# sdram_rev.net
KiCad netlist of a schematic drawn in Altium Designer
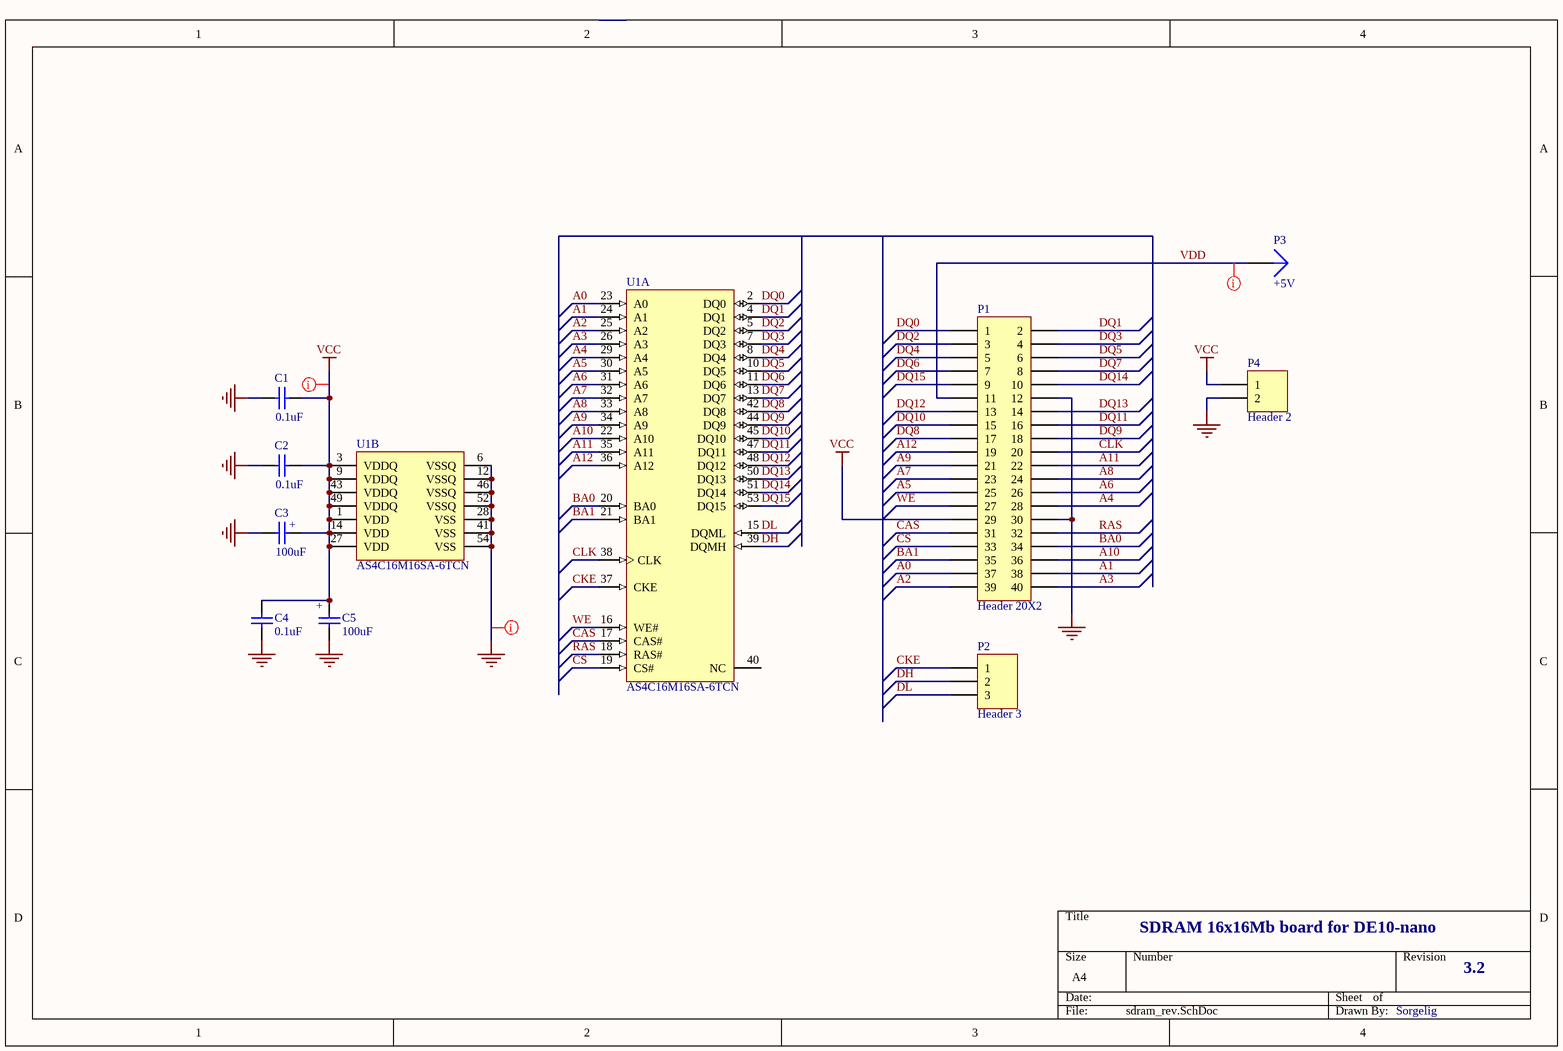
[diagram p0: sdram_rev.SchDoc]

(export (version "E")
  (design (tool "Eeschema 10.0.6"))
  (components
    (comp (ref "C1")
      (value "0.1uF")
      (footprint "0805")
      (description "Ceramic Chip Capacitor - Standard")
      (fields (field (name "Comment") "C0805") (field (name "PUBLISHER") "Altium Limited"))
      (libsource (lib "KEMET Chip Capacitor") (part "C0805"))
    )
    (comp (ref "C2")
      (value "0.1uF")
      (footprint "0805")
      (description "Ceramic Chip Capacitor - Standard")
      (fields (field (name "Comment") "C0805") (field (name "PUBLISHER") "Altium Limited"))
      (libsource (lib "KEMET Chip Capacitor") (part "C0805"))
    )
    (comp (ref "C3")
      (value "+")
      (footprint "0805")
      (description "Ceramic Chip Capacitor - Standard")
      (fields (field (name "ALTIUM_VALUE") "100uF") (field (name "PUBLISHER") "Altium Limited"))
      (libsource (lib "KEMET Chip Capacitor") (part "C0805"))
    )
    (comp (ref "C4")
      (value "0.1uF")
      (footprint "0805")
      (description "Ceramic Chip Capacitor - Standard")
      (fields (field (name "Comment") "C0805") (field (name "PUBLISHER") "Altium Limited"))
      (libsource (lib "KEMET Chip Capacitor") (part "C0805"))
    )
    (comp (ref "C5")
      (value "+")
      (footprint "0805")
      (description "Ceramic Chip Capacitor - Standard")
      (fields (field (name "ALTIUM_VALUE") "100uF") (field (name "PUBLISHER") "Altium Limited"))
      (libsource (lib "KEMET Chip Capacitor") (part "C0805"))
    )
    (comp (ref "P1")
      (value "Header 20X2")
      (footprint "HDR2X20")
      (description "Header, 20-Pin, Dual row")
      (fields (field (name "PUBLISHER") "Altium Limited"))
      (libsource (lib "Miscellaneous Connectors") (part "Header 20X2"))
    )
    (comp (ref "P2")
      (value "Header 3")
      (footprint "HDR1X3")
      (description "Header, 3-Pin")
      (fields (field (name "PUBLISHER") "Altium Limited"))
      (libsource (lib "Miscellaneous Connectors") (part "Header 3"))
    )
    (comp (ref "P3")
      (value "+5V")
      (footprint "PIN1")
      (description "Plug")
      (fields (field (name "PUBLISHER") "Altium Limited"))
      (libsource (lib "Miscellaneous Connectors") (part "Plug"))
    )
    (comp (ref "P4")
      (value "Header 2")
      (footprint "HDR1X2")
      (description "Header, 2-Pin")
      (fields (field (name "PUBLISHER") "Altium Limited"))
      (libsource (lib "Miscellaneous Connectors") (part "Header 2"))
    )
    (comp (ref "U1")
      (value "AS4C16M16SA-6TCN")
      (footprint "MICT-P-54_N")
      (description "256Mb PC133 SDR SDRAM, 16Mb x 16, 6ns, 3.3V, 0 to 70 degC, 54-Pin TSOP, Pb-Free")
      (fields (field (name "VOLTAGE") "3.3V ") (field (name "MANUFACTURER") "Micron"))
      (libsource (lib "Micron Memory SDRAM") (part "MT48LC16M16A2P-6A"))
    )
  )
  (nets
    (net (code "1") (name "/A0") (class "Default")
      (node (ref "P1") (pin "37") (pinfunction "37_37") (pintype "passive"))
      (node (ref "U1") (pin "23") (pinfunction "A0_23") (pintype "input"))
    )
    (net (code "2") (name "/A1") (class "Default")
      (node (ref "P1") (pin "38") (pinfunction "38_38") (pintype "passive"))
      (node (ref "U1") (pin "24") (pinfunction "A1_24") (pintype "input"))
    )
    (net (code "3") (name "/A2") (class "Default")
      (node (ref "P1") (pin "39") (pinfunction "39_39") (pintype "passive"))
      (node (ref "U1") (pin "25") (pinfunction "A2_25") (pintype "input"))
    )
    (net (code "4") (name "/A3") (class "Default")
      (node (ref "P1") (pin "40") (pinfunction "40_40") (pintype "passive"))
      (node (ref "U1") (pin "26") (pinfunction "A3_26") (pintype "input"))
    )
    (net (code "5") (name "/A4") (class "Default")
      (node (ref "P1") (pin "28") (pinfunction "28_28") (pintype "passive"))
      (node (ref "U1") (pin "29") (pinfunction "A4_29") (pintype "input"))
    )
    (net (code "6") (name "/A5") (class "Default")
      (node (ref "P1") (pin "25") (pinfunction "25_25") (pintype "passive"))
      (node (ref "U1") (pin "30") (pinfunction "A5_30") (pintype "input"))
    )
    (net (code "7") (name "/A6") (class "Default")
      (node (ref "P1") (pin "26") (pinfunction "26_26") (pintype "passive"))
      (node (ref "U1") (pin "31") (pinfunction "A6_31") (pintype "input"))
    )
    (net (code "8") (name "/A7") (class "Default")
      (node (ref "P1") (pin "23") (pinfunction "23_23") (pintype "passive"))
      (node (ref "U1") (pin "32") (pinfunction "A7_32") (pintype "input"))
    )
    (net (code "9") (name "/A8") (class "Default")
      (node (ref "P1") (pin "24") (pinfunction "24_24") (pintype "passive"))
      (node (ref "U1") (pin "33") (pinfunction "A8_33") (pintype "input"))
    )
    (net (code "10") (name "/A9") (class "Default")
      (node (ref "P1") (pin "21") (pinfunction "21_21") (pintype "passive"))
      (node (ref "U1") (pin "34") (pinfunction "A9_34") (pintype "input"))
    )
    (net (code "11") (name "/A10") (class "Default")
      (node (ref "P1") (pin "36") (pinfunction "36_36") (pintype "passive"))
      (node (ref "U1") (pin "22") (pinfunction "A10_22") (pintype "input"))
    )
    (net (code "12") (name "/A11") (class "Default")
      (node (ref "P1") (pin "22") (pinfunction "22_22") (pintype "passive"))
      (node (ref "U1") (pin "35") (pinfunction "A11_35") (pintype "input"))
    )
    (net (code "13") (name "/A12") (class "Default")
      (node (ref "P1") (pin "19") (pinfunction "19_19") (pintype "passive"))
      (node (ref "U1") (pin "36") (pinfunction "A12_36") (pintype "input"))
    )
    (net (code "14") (name "/BA0") (class "Default")
      (node (ref "P1") (pin "34") (pinfunction "34_34") (pintype "passive"))
      (node (ref "U1") (pin "20") (pinfunction "BA0_20") (pintype "input"))
    )
    (net (code "15") (name "/BA1") (class "Default")
      (node (ref "P1") (pin "35") (pinfunction "35_35") (pintype "passive"))
      (node (ref "U1") (pin "21") (pinfunction "BA1_21") (pintype "input"))
    )
    (net (code "16") (name "/CAS") (class "Default")
      (node (ref "P1") (pin "31") (pinfunction "31_31") (pintype "passive"))
      (node (ref "U1") (pin "17") (pinfunction "CAS#_17") (pintype "input"))
    )
    (net (code "17") (name "/CKE") (class "Default")
      (node (ref "P2") (pin "1") (pinfunction "1_1") (pintype "passive"))
      (node (ref "U1") (pin "37") (pinfunction "CKE_37") (pintype "input"))
    )
    (net (code "18") (name "/CLK") (class "Default")
      (node (ref "P1") (pin "20") (pinfunction "20_20") (pintype "passive"))
      (node (ref "U1") (pin "38") (pinfunction "CLK_38") (pintype "input"))
    )
    (net (code "19") (name "/CS") (class "Default")
      (node (ref "P1") (pin "33") (pinfunction "33_33") (pintype "passive"))
      (node (ref "U1") (pin "19") (pinfunction "CS#_19") (pintype "input"))
    )
    (net (code "20") (name "/DH") (class "Default")
      (node (ref "P2") (pin "2") (pinfunction "2_2") (pintype "passive"))
      (node (ref "U1") (pin "39") (pinfunction "DQMH_39") (pintype "input"))
    )
    (net (code "21") (name "/DL") (class "Default")
      (node (ref "P2") (pin "3") (pinfunction "3_3") (pintype "passive"))
      (node (ref "U1") (pin "15") (pinfunction "DQML_15") (pintype "input"))
    )
    (net (code "22") (name "/DQ0") (class "Default")
      (node (ref "P1") (pin "1") (pinfunction "1_1") (pintype "passive"))
      (node (ref "U1") (pin "2") (pinfunction "DQ0_2") (pintype "bidirectional"))
    )
    (net (code "23") (name "/DQ1") (class "Default")
      (node (ref "P1") (pin "2") (pinfunction "2_2") (pintype "passive"))
      (node (ref "U1") (pin "4") (pinfunction "DQ1_4") (pintype "bidirectional"))
    )
    (net (code "24") (name "/DQ2") (class "Default")
      (node (ref "P1") (pin "3") (pinfunction "3_3") (pintype "passive"))
      (node (ref "U1") (pin "5") (pinfunction "DQ2_5") (pintype "bidirectional"))
    )
    (net (code "25") (name "/DQ3") (class "Default")
      (node (ref "P1") (pin "4") (pinfunction "4_4") (pintype "passive"))
      (node (ref "U1") (pin "7") (pinfunction "DQ3_7") (pintype "bidirectional"))
    )
    (net (code "26") (name "/DQ4") (class "Default")
      (node (ref "P1") (pin "5") (pinfunction "5_5") (pintype "passive"))
      (node (ref "U1") (pin "8") (pinfunction "DQ4_8") (pintype "bidirectional"))
    )
    (net (code "27") (name "/DQ5") (class "Default")
      (node (ref "P1") (pin "6") (pinfunction "6_6") (pintype "passive"))
      (node (ref "U1") (pin "10") (pinfunction "DQ5_10") (pintype "bidirectional"))
    )
    (net (code "28") (name "/DQ6") (class "Default")
      (node (ref "P1") (pin "7") (pinfunction "7_7") (pintype "passive"))
      (node (ref "U1") (pin "11") (pinfunction "DQ6_11") (pintype "bidirectional"))
    )
    (net (code "29") (name "/DQ7") (class "Default")
      (node (ref "P1") (pin "8") (pinfunction "8_8") (pintype "passive"))
      (node (ref "U1") (pin "13") (pinfunction "DQ7_13") (pintype "bidirectional"))
    )
    (net (code "30") (name "/DQ8") (class "Default")
      (node (ref "P1") (pin "17") (pinfunction "17_17") (pintype "passive"))
      (node (ref "U1") (pin "42") (pinfunction "DQ8_42") (pintype "bidirectional"))
    )
    (net (code "31") (name "/DQ9") (class "Default")
      (node (ref "P1") (pin "18") (pinfunction "18_18") (pintype "passive"))
      (node (ref "U1") (pin "44") (pinfunction "DQ9_44") (pintype "bidirectional"))
    )
    (net (code "32") (name "/DQ10") (class "Default")
      (node (ref "P1") (pin "15") (pinfunction "15_15") (pintype "passive"))
      (node (ref "U1") (pin "45") (pinfunction "DQ10_45") (pintype "bidirectional"))
    )
    (net (code "33") (name "/DQ11") (class "Default")
      (node (ref "P1") (pin "16") (pinfunction "16_16") (pintype "passive"))
      (node (ref "U1") (pin "47") (pinfunction "DQ11_47") (pintype "bidirectional"))
    )
    (net (code "34") (name "/DQ12") (class "Default")
      (node (ref "P1") (pin "13") (pinfunction "13_13") (pintype "passive"))
      (node (ref "U1") (pin "48") (pinfunction "DQ12_48") (pintype "bidirectional"))
    )
    (net (code "35") (name "/DQ13") (class "Default")
      (node (ref "P1") (pin "14") (pinfunction "14_14") (pintype "passive"))
      (node (ref "U1") (pin "50") (pinfunction "DQ13_50") (pintype "bidirectional"))
    )
    (net (code "36") (name "/DQ14") (class "Default")
      (node (ref "P1") (pin "10") (pinfunction "10_10") (pintype "passive"))
      (node (ref "U1") (pin "51") (pinfunction "DQ14_51") (pintype "bidirectional"))
    )
    (net (code "37") (name "/DQ15") (class "Default")
      (node (ref "P1") (pin "9") (pinfunction "9_9") (pintype "passive"))
      (node (ref "U1") (pin "53") (pinfunction "DQ15_53") (pintype "bidirectional"))
    )
    (net (code "38") (name "/RAS") (class "Default")
      (node (ref "P1") (pin "32") (pinfunction "32_32") (pintype "passive"))
      (node (ref "U1") (pin "18") (pinfunction "RAS#_18") (pintype "input"))
    )
    (net (code "39") (name "/VDD") (class "Default")
      (node (ref "P1") (pin "11") (pinfunction "11_11") (pintype "power_in"))
      (node (ref "P3") (pin "1") (pinfunction "1_1") (pintype "passive"))
    )
    (net (code "40") (name "/WE") (class "Default")
      (node (ref "P1") (pin "27") (pinfunction "27_27") (pintype "passive"))
      (node (ref "U1") (pin "16") (pinfunction "WE#_16") (pintype "input"))
    )
    (net (code "41") (name "GND") (class "Default")
      (node (ref "C1") (pin "1") (pinfunction "1_1") (pintype "passive"))
      (node (ref "C2") (pin "1") (pinfunction "1_1") (pintype "passive"))
      (node (ref "C3") (pin "1") (pinfunction "1_1") (pintype "passive"))
      (node (ref "C4") (pin "1") (pinfunction "1_1") (pintype "passive"))
      (node (ref "C5") (pin "1") (pinfunction "1_1") (pintype "passive"))
      (node (ref "P1") (pin "12") (pinfunction "12_12") (pintype "power_in"))
      (node (ref "P1") (pin "30") (pinfunction "30_30") (pintype "power_in"))
      (node (ref "P4") (pin "2") (pinfunction "2_2") (pintype "passive"))
      (node (ref "U1") (pin "12") (pinfunction "VSSQ_12") (pintype "power_in"))
      (node (ref "U1") (pin "28") (pinfunction "VSS_28") (pintype "power_in"))
      (node (ref "U1") (pin "41") (pinfunction "VSS_41") (pintype "power_in"))
      (node (ref "U1") (pin "46") (pinfunction "VSSQ_46") (pintype "power_in"))
      (node (ref "U1") (pin "52") (pinfunction "VSSQ_52") (pintype "power_in"))
      (node (ref "U1") (pin "54") (pinfunction "VSS_54") (pintype "power_in"))
      (node (ref "U1") (pin "6") (pinfunction "VSSQ_6") (pintype "power_in"))
    )
    (net (code "42") (name "VCC") (class "Default")
      (node (ref "C1") (pin "2") (pinfunction "2_2") (pintype "passive"))
      (node (ref "C2") (pin "2") (pinfunction "2_2") (pintype "passive"))
      (node (ref "C3") (pin "2") (pinfunction "2_2") (pintype "passive"))
      (node (ref "C4") (pin "2") (pinfunction "2_2") (pintype "passive"))
      (node (ref "C5") (pin "2") (pinfunction "2_2") (pintype "passive"))
      (node (ref "P1") (pin "29") (pinfunction "29_29") (pintype "power_in"))
      (node (ref "P4") (pin "1") (pinfunction "1_1") (pintype "passive"))
      (node (ref "U1") (pin "1") (pinfunction "VDD_1") (pintype "power_in"))
      (node (ref "U1") (pin "14") (pinfunction "VDD_14") (pintype "power_in"))
      (node (ref "U1") (pin "27") (pinfunction "VDD_27") (pintype "power_in"))
      (node (ref "U1") (pin "3") (pinfunction "VDDQ_3") (pintype "power_in"))
      (node (ref "U1") (pin "43") (pinfunction "VDDQ_43") (pintype "power_in"))
      (node (ref "U1") (pin "49") (pinfunction "VDDQ_49") (pintype "power_in"))
      (node (ref "U1") (pin "9") (pinfunction "VDDQ_9") (pintype "power_in"))
    )
    (net (code "43") (name "unconnected-(U1A-NC-Pad40)") (class "Default")
      (node (ref "U1") (pin "40") (pinfunction "NC_40") (pintype "passive"))
    )
  )
)
